# drvoutput3.net
KiCad netlist of a schematic drawn in Altium Designer
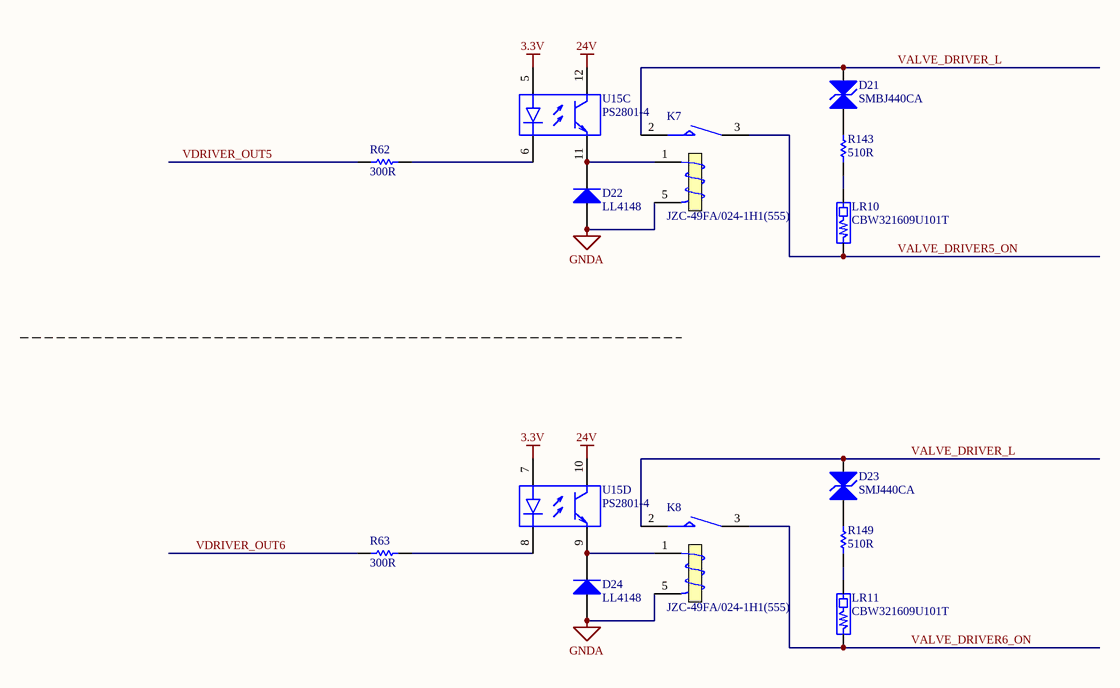
[diagram p0: drvoutput3.SchDoc]

(export (version "E")
  (design (tool "Eeschema 10.0.6"))
  (components
    (comp (ref "D21")
      (value "SMBJ440CA")
      (footprint "SMB")
      (description "Bi-dir TVS Diode")
      (fields (field (name "PUBLISHER") "Altium Limited"))
      (libsource (lib "UserLib") (part "Bi-dir TVS Diode"))
    )
    (comp (ref "D22")
      (value "LL4148")
      (footprint "CD2012-0805")
      (description "1 Amp General Purpose Rectifier")
      (fields (field (name "PUBLISHER") "Altium Limited"))
      (libsource (lib "Miscellaneous Devices") (part "Diode 1N4007"))
    )
    (comp (ref "D23")
      (value "SMJ440CA")
      (footprint "SMB")
      (description "Bi-dir TVS Diode")
      (fields (field (name "PUBLISHER") "Altium Limited"))
      (libsource (lib "UserLib") (part "Bi-dir TVS Diode"))
    )
    (comp (ref "D24")
      (value "LL4148")
      (footprint "CD2012-0805")
      (description "1 Amp General Purpose Rectifier")
      (fields (field (name "PUBLISHER") "Altium Limited"))
      (libsource (lib "Miscellaneous Devices") (part "Diode 1N4007"))
    )
    (comp (ref "K7")
      (value "JZC-49FA/024-1H1(555)")
      (footprint "JZC-49FA")
      (description "Intermediate  Power  Relay")
      (fields (field (name "PUBLISHER") "Altium Limited"))
      (libsource (lib "UserSchDev") (part "JZC-49FA"))
    )
    (comp (ref "K8")
      (value "JZC-49FA/024-1H1(555)")
      (footprint "JZC-49FA")
      (description "Intermediate  Power  Relay")
      (fields (field (name "PUBLISHER") "Altium Limited"))
      (libsource (lib "UserSchDev") (part "JZC-49FA"))
    )
    (comp (ref "LR10")
      (value "CBW321609U101T")
      (footprint "INDC3216M")
      (description "EMI FILTERS,DC Resistance max.0.05~1.5 ohms,10 ~ 1000 ohms at 100MHz  Frequency")
      (libsource (lib "UserLib") (part "BLM10/11/21/31/41"))
    )
    (comp (ref "LR11")
      (value "CBW321609U101T")
      (footprint "INDC3216M")
      (description "EMI FILTERS,DC Resistance max.0.05~1.5 ohms,10 ~ 1000 ohms at 100MHz  Frequency")
      (libsource (lib "UserLib") (part "BLM10/11/21/31/41"))
    )
    (comp (ref "R62")
      (value "300R")
      (footprint "RESC2012M")
      (description "Resistor")
      (fields (field (name "PUBLISHER") "Altium Limited"))
      (libsource (lib "Miscellaneous Devices") (part "Res1"))
    )
    (comp (ref "R63")
      (value "300R")
      (footprint "RESC2012M")
      (description "Resistor")
      (fields (field (name "PUBLISHER") "Altium Limited"))
      (libsource (lib "Miscellaneous Devices") (part "Res1"))
    )
    (comp (ref "R143")
      (value "510R")
      (footprint "RESC3216M")
      (description "Metal film Resistor")
      (fields (field (name "PUBLISHER") "Altium Limited"))
      (libsource (lib "Miscellaneous Devices") (part "Res1"))
    )
    (comp (ref "R149")
      (value "510R")
      (footprint "RESC3216M")
      (description "Metal film Resistor")
      (fields (field (name "PUBLISHER") "Altium Limited"))
      (libsource (lib "Miscellaneous Devices") (part "Res1"))
    )
    (comp (ref "U15")
      (value "PS2801-4")
      (footprint "SOIC16_N")
      (fields (field (name "PUBLISHER") "Altium Limited"))
      (libsource (lib "UserSchDev") (part "PS2801-4"))
    )
  )
  (nets
    (net (code "1") (name "/VALVE_DRIVER5_ON") (class "Default")
      (node (ref "K7") (pin "3") (pinfunction "NO_3") (pintype "passive"))
      (node (ref "LR10") (pin "1") (pinfunction "1_1") (pintype "passive"))
    )
    (net (code "2") (name "/VALVE_DRIVER6_ON") (class "Default")
      (node (ref "K8") (pin "3") (pinfunction "NO_3") (pintype "passive"))
      (node (ref "LR11") (pin "1") (pinfunction "1_1") (pintype "passive"))
    )
    (net (code "3") (name "/VALVE_DRIVER_L") (class "Default")
      (node (ref "D21") (pin "2") (pinfunction "K_2") (pintype "passive"))
      (node (ref "D23") (pin "2") (pinfunction "K_2") (pintype "passive"))
      (node (ref "K7") (pin "2") (pinfunction "COM_2") (pintype "passive"))
      (node (ref "K8") (pin "2") (pinfunction "COM_2") (pintype "passive"))
    )
    (net (code "4") (name "/VDRIVER_OUT5") (class "Default")
      (node (ref "R62") (pin "1") (pinfunction "1_1") (pintype "passive"))
    )
    (net (code "5") (name "/VDRIVER_OUT6") (class "Default")
      (node (ref "R63") (pin "1") (pinfunction "1_1") (pintype "passive"))
    )
    (net (code "6") (name "3.3V") (class "Default")
      (node (ref "U15") (pin "5") (pinfunction "+_5") (pintype "passive"))
      (node (ref "U15") (pin "7") (pinfunction "+_7") (pintype "passive"))
    )
    (net (code "7") (name "24V") (class "Default")
      (node (ref "U15") (pin "10") (pinfunction "C_10") (pintype "passive"))
      (node (ref "U15") (pin "12") (pinfunction "C_12") (pintype "passive"))
    )
    (net (code "8") (name "GNDA") (class "Default")
      (node (ref "D22") (pin "1") (pinfunction "A_1") (pintype "passive"))
      (node (ref "D24") (pin "1") (pinfunction "A_1") (pintype "passive"))
      (node (ref "K7") (pin "5") (pinfunction "T2_5") (pintype "passive"))
      (node (ref "K8") (pin "5") (pinfunction "T2_5") (pintype "passive"))
    )
    (net (code "9") (name "Net-(D21-A)") (class "Default")
      (node (ref "D21") (pin "1") (pinfunction "A_1") (pintype "passive"))
      (node (ref "R143") (pin "2") (pinfunction "2_2") (pintype "passive"))
    )
    (net (code "10") (name "Net-(D22-K)") (class "Default")
      (node (ref "D22") (pin "2") (pinfunction "K_2") (pintype "passive"))
      (node (ref "K7") (pin "1") (pinfunction "1_1") (pintype "passive"))
      (node (ref "U15") (pin "11") (pinfunction "E_11") (pintype "passive"))
    )
    (net (code "11") (name "Net-(D23-A)") (class "Default")
      (node (ref "D23") (pin "1") (pinfunction "A_1") (pintype "passive"))
      (node (ref "R149") (pin "2") (pinfunction "2_2") (pintype "passive"))
    )
    (net (code "12") (name "Net-(D24-K)") (class "Default")
      (node (ref "D24") (pin "2") (pinfunction "K_2") (pintype "passive"))
      (node (ref "K8") (pin "1") (pinfunction "1_1") (pintype "passive"))
      (node (ref "U15") (pin "9") (pinfunction "E_9") (pintype "passive"))
    )
    (net (code "13") (name "Net-(LR10-Pad2)") (class "Default")
      (node (ref "LR10") (pin "2") (pinfunction "2_2") (pintype "passive"))
      (node (ref "R143") (pin "1") (pinfunction "1_1") (pintype "passive"))
    )
    (net (code "14") (name "Net-(LR11-Pad2)") (class "Default")
      (node (ref "LR11") (pin "2") (pinfunction "2_2") (pintype "passive"))
      (node (ref "R149") (pin "1") (pinfunction "1_1") (pintype "passive"))
    )
    (net (code "15") (name "Net-(U15C--)") (class "Default")
      (node (ref "R62") (pin "2") (pinfunction "2_2") (pintype "passive"))
      (node (ref "U15") (pin "6") (pinfunction "-_6") (pintype "passive"))
    )
    (net (code "16") (name "Net-(U15D--)") (class "Default")
      (node (ref "R63") (pin "2") (pinfunction "2_2") (pintype "passive"))
      (node (ref "U15") (pin "8") (pinfunction "-_8") (pintype "passive"))
    )
  )
)
